# WIF_PCB.net
KiCad netlist of a schematic drawn in EasyEDA Pro
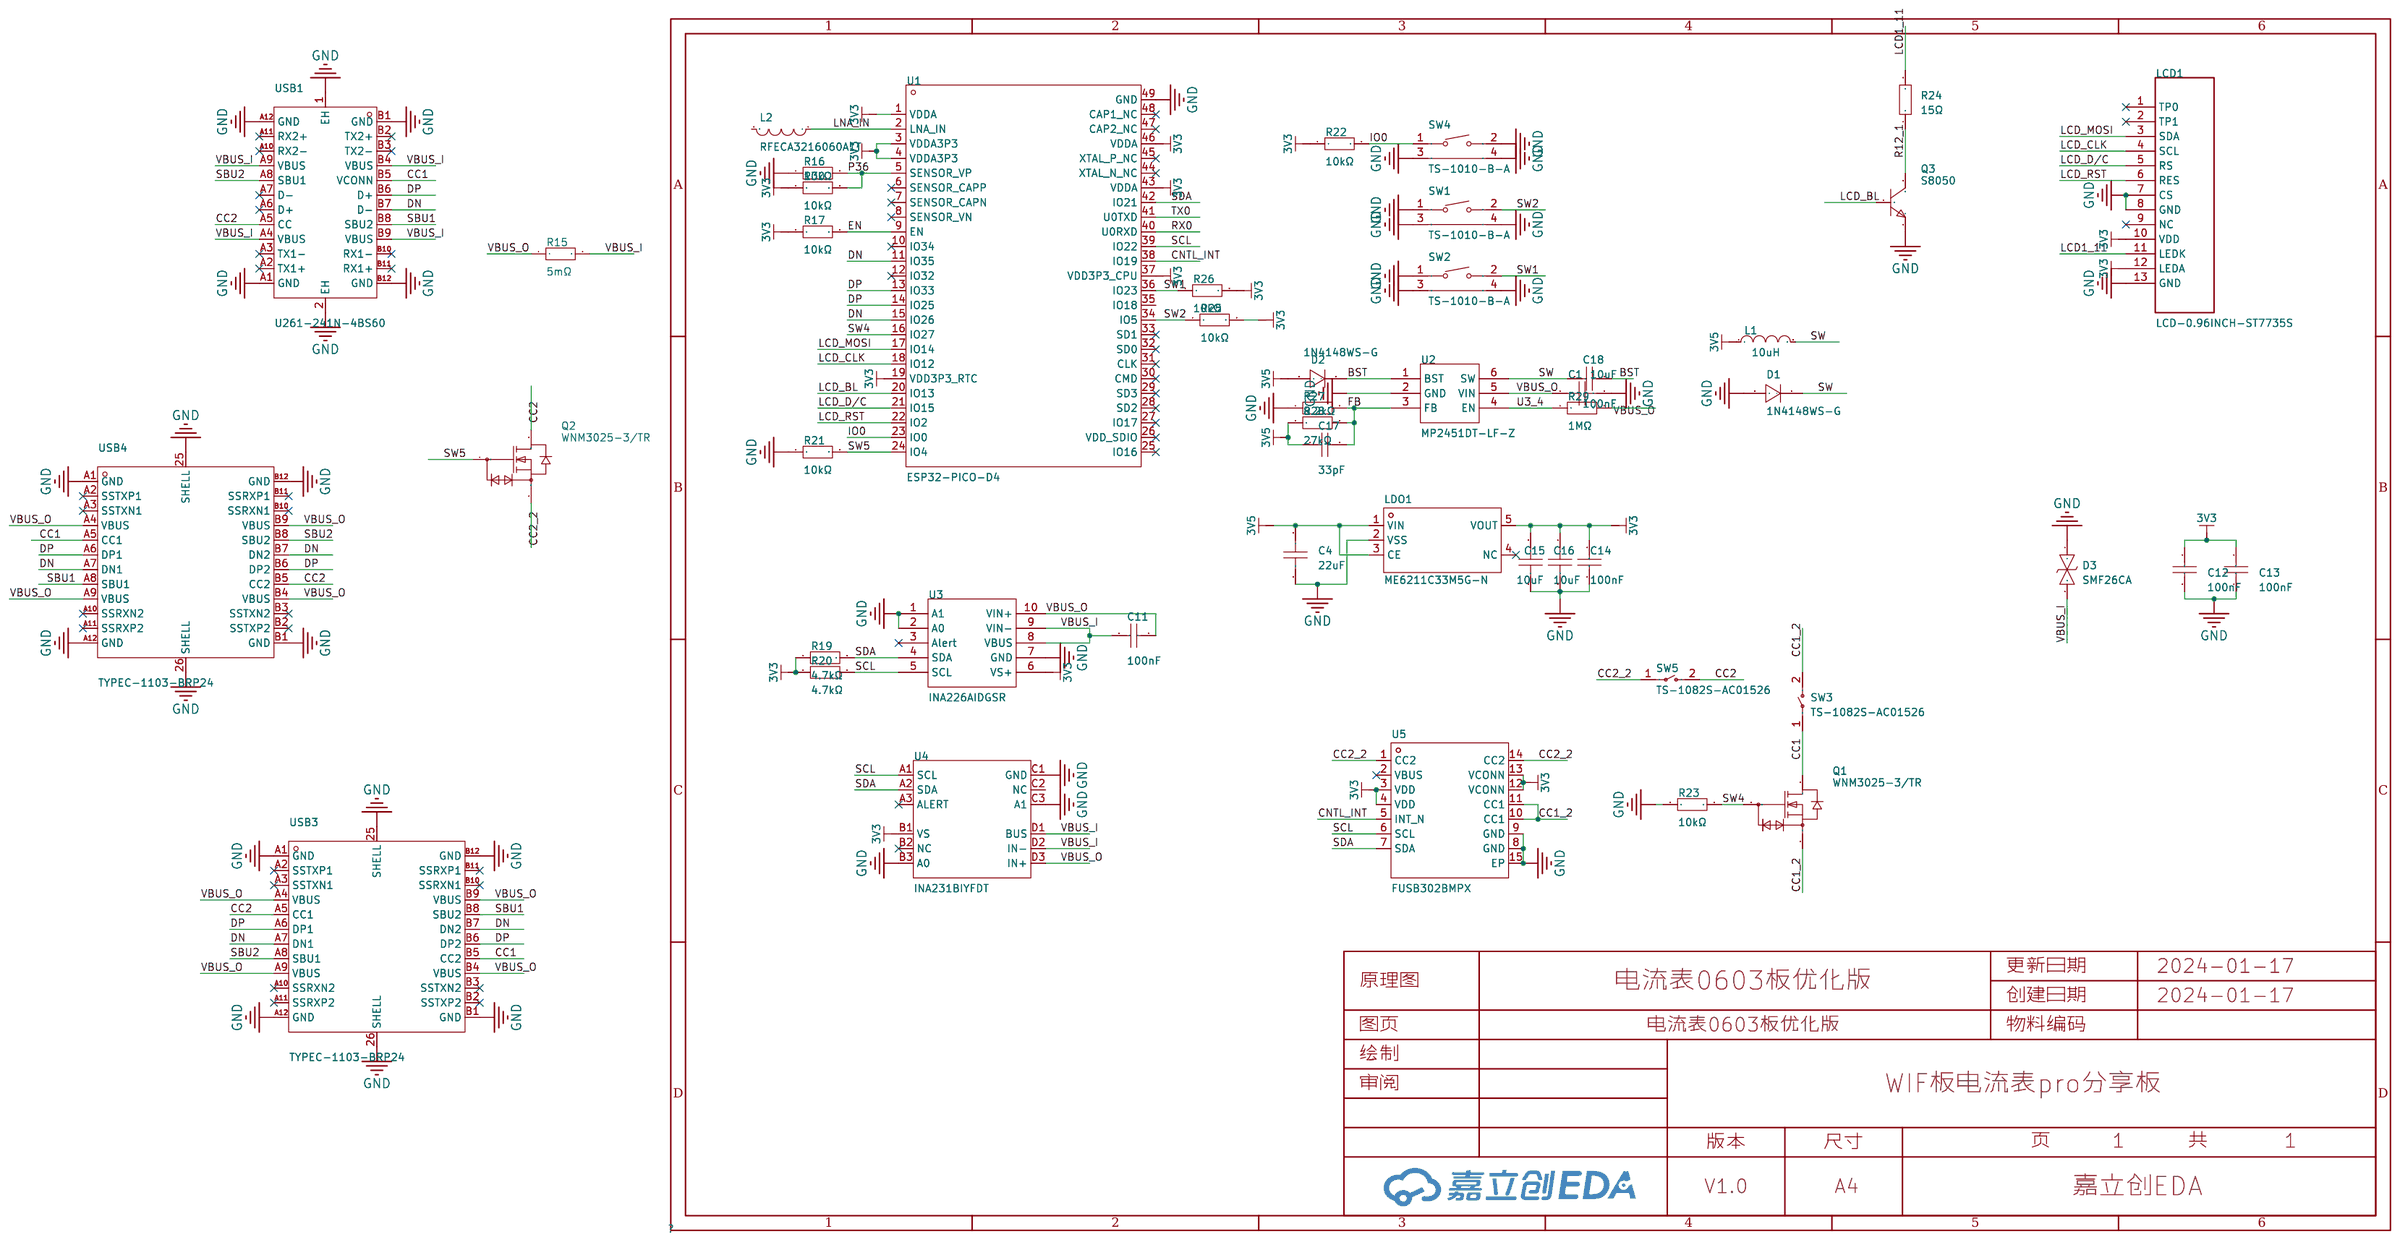
[diagram p0: schematic sheet]

(export (version "E")
  (design (tool "Eeschema 10.0.6"))
  (components
    (comp (ref "C1")
      (value "10uF")
      (footprint "easyedapro:C0603")
      (description "容值:10uF;精度:±20%;额定电压:25V;材质(温度系数):X5R;")
      (fields
        (field (name "Manufacturer Part") "CL10A106MA8NRNC")
        (field (name "Manufacturer") "SAMSUNG(三星)")
      )
      (libsource (lib "easyedapro") (part "CL10A106MA8NRNC"))
    )
    (comp (ref "C4")
      (value "22uF")
      (footprint "easyedapro:C0603")
      (description "容值:22uF;精度:±20%;额定电压:6.3V;材质(温度系数):X5R;")
      (fields
        (field (name "Manufacturer Part") "CL10A226MQ8NRNC")
        (field (name "Manufacturer") "SAMSUNG(三星)")
      )
      (libsource (lib "easyedapro") (part "CL10A226MQ8NRNC"))
    )
    (comp (ref "C11")
      (value "100nF")
      (footprint "easyedapro:C0603")
      (description "容值:100nF;精度:±10%;额定电压:50V;材质(温度系数):X7R;")
      (fields (field (name "Manufacturer Part") "0603B104K500NT") (field (name "Manufacturer") "FH(风华)"))
      (libsource (lib "easyedapro") (part "0603B104K500NT"))
    )
    (comp (ref "C12")
      (value "100nF")
      (footprint "easyedapro:C0603")
      (description "容值:100nF;精度:±10%;额定电压:50V;材质(温度系数):X7R;")
      (fields (field (name "Manufacturer Part") "0603B104K500NT") (field (name "Manufacturer") "FH(风华)"))
      (libsource (lib "easyedapro") (part "0603B104K500NT"))
    )
    (comp (ref "C13")
      (value "100nF")
      (footprint "easyedapro:C0603")
      (description "容值:100nF;精度:±10%;额定电压:50V;材质(温度系数):X7R;")
      (fields (field (name "Manufacturer Part") "0603B104K500NT") (field (name "Manufacturer") "FH(风华)"))
      (libsource (lib "easyedapro") (part "0603B104K500NT"))
    )
    (comp (ref "C14")
      (value "100nF")
      (footprint "easyedapro:C0603")
      (description "容值:100nF;精度:±10%;额定电压:50V;材质(温度系数):X7R;")
      (fields (field (name "Manufacturer Part") "0603B104K500NT") (field (name "Manufacturer") "FH(风华)"))
      (libsource (lib "easyedapro") (part "0603B104K500NT"))
    )
    (comp (ref "C15")
      (value "10uF")
      (footprint "easyedapro:C0603")
      (description "容值:10uF;精度:±10%;额定电压:10V;材质(温度系数):X5R;")
      (fields
        (field (name "Manufacturer Part") "CL10A106KP8NNNC")
        (field (name "Manufacturer") "SAMSUNG(三星)")
      )
      (libsource (lib "easyedapro") (part "CL10A106KP8NNNC"))
    )
    (comp (ref "C16")
      (value "10uF")
      (footprint "easyedapro:C0603")
      (description "容值:10uF;精度:±10%;额定电压:10V;材质(温度系数):X5R;")
      (fields
        (field (name "Manufacturer Part") "CL10A106KP8NNNC")
        (field (name "Manufacturer") "SAMSUNG(三星)")
      )
      (libsource (lib "easyedapro") (part "CL10A106KP8NNNC"))
    )
    (comp (ref "C17")
      (value "33pF")
      (footprint "easyedapro:C0603")
      (description "容值:33pF;精度:±5%;额定电压:50V;材质(温度系数):C0G;")
      (fields
        (field (name "Manufacturer Part") "CL10C330JB8NNNC")
        (field (name "Manufacturer") "SAMSUNG(三星)")
      )
      (libsource (lib "easyedapro") (part "CL10C330JB8NNNC"))
    )
    (comp (ref "C18")
      (value "100nF")
      (footprint "easyedapro:C0603")
      (description "容值:100nF;精度:±10%;额定电压:50V;材质(温度系数):X7R;")
      (fields (field (name "Manufacturer Part") "0603B104K500NT") (field (name "Manufacturer") "FH(风华)"))
      (libsource (lib "easyedapro") (part "0603B104K500NT"))
    )
    (comp (ref "D1")
      (value "1N4148WS-G")
      (footprint "easyedapro:SOD-323_L1.7-W1.3-LS2.7-RD")
      (description "二极管配置:独立式;正向压降(Vf):1.25V@150mA;直流反向耐压(Vr):100V;平均整流电流(Io):150mA;功率:200mW;反向恢复时间(trr):4ns;")
      (fields (field (name "Manufacturer") "CJ(江苏长电/长晶)"))
      (libsource (lib "easyedapro") (part "1N4148WS-G"))
    )
    (comp (ref "D2")
      (value "1N4148WS-G")
      (footprint "easyedapro:SOD-323_L1.7-W1.3-LS2.7-RD")
      (description "二极管配置:独立式;正向压降(Vf):1.25V@150mA;直流反向耐压(Vr):100V;平均整流电流(Io):150mA;功率:200mW;反向恢复时间(trr):4ns;")
      (fields (field (name "Manufacturer") "CJ(江苏长电/长晶)"))
      (libsource (lib "easyedapro") (part "1N4148WS-G"))
    )
    (comp (ref "D3")
      (value "SMF26CA")
      (footprint "easyedapro:SOD-123_L2.8-W1.8-LS3.7-BI")
      (description "极性:双向;反向截止电压(Vrwm):26V;击穿电压:28.9V;峰值脉冲电流(Ipp)@10/1000μs:4.8A;最大钳位电压:42.1V;")
      (fields (field (name "Manufacturer") "AnBon(安邦)"))
      (libsource (lib "easyedapro") (part "SMF26CA_C435495"))
    )
    (comp (ref "L1")
      (value "10uH")
      (footprint "easyedapro:IND-SMD_L4.4-W4.0_PHC0420")
      (description "电感值:10uH;精度:±20%;额定电流:1.6A;")
      (fields (field (name "Manufacturer Part") "PHC0420-100M-T") (field (name "Manufacturer") "EMTEK(兆欣)"))
      (libsource (lib "easyedapro") (part "PHC0420-100M-T"))
    )
    (comp (ref "L2")
      (value "RFECA3216060A1T")
      (footprint "easyedapro:ANT-SMD_L3.1-W1.6")
      (description "2.4 GHz 陶瓷天线")
      (fields (field (name "Manufacturer") "Walsin(华新科)"))
      (libsource (lib "easyedapro") (part "RFECA3216060A1T"))
    )
    (comp (ref "LCD1")
      (value "LCD-0.96INCH-ST7735S")
      (footprint "easyedapro:LCD-0.96INCH-IPS-TFT-16080-ST7735S")
      (libsource (lib "easyedapro") (part "LCD-0.96INCH-ST7735S-1"))
    )
    (comp (ref "LDO1")
      (value "ME6211C33M5G-N")
      (footprint "easyedapro:SOT-23-5_L3.0-W1.7-P0.95-LS2.8-BL")
      (description "输出类型:固定;输出极性:正;最大输入电压:6V;输出电压:3.3V;输出电流:500mA;电源纹波抑制比(PSRR):70dB;")
      (fields (field (name "Manufacturer") "MICRONE(南京微盟)"))
      (libsource (lib "easyedapro") (part "ME6211C33M5G-N"))
    )
    (comp (ref "Q1")
      (value "WNM3025-3/TR")
      (footprint "easyedapro:X1-DFN1006-3_L1.0-W0.6-P0.35-BR")
      (fields (field (name "Manufacturer") "WILLSEMI(韦尔)"))
      (libsource (lib "easyedapro") (part "WNM3025-3/TR"))
    )
    (comp (ref "Q2")
      (value "WNM3025-3/TR")
      (footprint "easyedapro:X1-DFN1006-3_L1.0-W0.6-P0.35-BR")
      (fields (field (name "Manufacturer") "WILLSEMI(韦尔)"))
      (libsource (lib "easyedapro") (part "WNM3025-3/TR"))
    )
    (comp (ref "Q3")
      (value "S8050")
      (footprint "easyedapro:SOT-23-3_L2.9-W1.3-P1.90-LS2.4-BR")
      (description "晶体管类型:-;集电极电流(Ic):500mA;集射极击穿电压(Vceo):25V;功率(Pd):300mW;")
      (fields (field (name "Manufacturer") "JSMSEMI(杰盛微)"))
      (libsource (lib "easyedapro") (part "S8050"))
    )
    (comp (ref "R15")
      (value "5mΩ")
      (footprint "easyedapro:R2512")
      (description "阻值:5mΩ;精度:±1%;功率:3W;温度系数:±25ppm/°C;")
      (fields (field (name "Manufacturer Part") "LR2512-23R005F4") (field (name "Manufacturer") "RALEC(旺诠)"))
      (libsource (lib "easyedapro") (part "LR2512-23R005F4"))
    )
    (comp (ref "R16")
      (value "10kΩ")
      (footprint "easyedapro:R0603")
      (description "阻值:10kΩ;精度:±1%;功率:100mW;温度系数:±100ppm/°C;电阻类型:厚膜电阻;")
      (fields
        (field (name "Manufacturer Part") "0603WAF1002T5E")
        (field (name "Manufacturer") "UNI-ROYAL(厚声)")
      )
      (libsource (lib "easyedapro") (part "0603WAF1002T5E"))
    )
    (comp (ref "R17")
      (value "10kΩ")
      (footprint "easyedapro:R0603")
      (description "阻值:10kΩ;精度:±1%;功率:100mW;温度系数:±100ppm/°C;电阻类型:厚膜电阻;")
      (fields
        (field (name "Manufacturer Part") "0603WAF1002T5E")
        (field (name "Manufacturer") "UNI-ROYAL(厚声)")
      )
      (libsource (lib "easyedapro") (part "0603WAF1002T5E"))
    )
    (comp (ref "R19")
      (value "4.7kΩ")
      (footprint "easyedapro:R0603")
      (description "阻值:4.7kΩ;精度:±1%;功率:100mW;温度系数:±100ppm/°C;电阻类型:厚膜电阻;")
      (fields
        (field (name "Manufacturer Part") "0603WAF4701T5E")
        (field (name "Manufacturer") "UNI-ROYAL(厚声)")
      )
      (libsource (lib "easyedapro") (part "0603WAF4701T5E"))
    )
    (comp (ref "R20")
      (value "4.7kΩ")
      (footprint "easyedapro:R0603")
      (description "阻值:4.7kΩ;精度:±1%;功率:100mW;温度系数:±100ppm/°C;电阻类型:厚膜电阻;")
      (fields
        (field (name "Manufacturer Part") "0603WAF4701T5E")
        (field (name "Manufacturer") "UNI-ROYAL(厚声)")
      )
      (libsource (lib "easyedapro") (part "0603WAF4701T5E"))
    )
    (comp (ref "R21")
      (value "10kΩ")
      (footprint "easyedapro:R0603")
      (description "阻值:10kΩ;精度:±1%;功率:100mW;温度系数:±100ppm/°C;电阻类型:厚膜电阻;")
      (fields
        (field (name "Manufacturer Part") "0603WAF1002T5E")
        (field (name "Manufacturer") "UNI-ROYAL(厚声)")
      )
      (libsource (lib "easyedapro") (part "0603WAF1002T5E"))
    )
    (comp (ref "R22")
      (value "10kΩ")
      (footprint "easyedapro:R0603")
      (description "阻值:10kΩ;精度:±1%;功率:100mW;温度系数:±100ppm/°C;电阻类型:厚膜电阻;")
      (fields
        (field (name "Manufacturer Part") "0603WAF1002T5E")
        (field (name "Manufacturer") "UNI-ROYAL(厚声)")
      )
      (libsource (lib "easyedapro") (part "0603WAF1002T5E"))
    )
    (comp (ref "R23")
      (value "10kΩ")
      (footprint "easyedapro:R0603")
      (description "阻值:10kΩ;精度:±1%;功率:100mW;温度系数:±100ppm/°C;电阻类型:厚膜电阻;")
      (fields
        (field (name "Manufacturer Part") "0603WAF1002T5E")
        (field (name "Manufacturer") "UNI-ROYAL(厚声)")
      )
      (libsource (lib "easyedapro") (part "0603WAF1002T5E"))
    )
    (comp (ref "R24")
      (value "15Ω")
      (footprint "easyedapro:R0603")
      (description "阻值:15Ω;精度:±1%;功率:100mW;温度系数:±100ppm/°C;电阻类型:厚膜电阻;")
      (fields
        (field (name "Manufacturer Part") "0603WAF150JT5E")
        (field (name "Manufacturer") "UNI-ROYAL(厚声)")
      )
      (libsource (lib "easyedapro") (part "0603WAF150JT5E"))
    )
    (comp (ref "R25")
      (value "10kΩ")
      (footprint "easyedapro:R0603")
      (description "阻值:10kΩ;精度:±1%;功率:100mW;温度系数:±100ppm/°C;电阻类型:厚膜电阻;")
      (fields
        (field (name "Manufacturer Part") "0603WAF1002T5E")
        (field (name "Manufacturer") "UNI-ROYAL(厚声)")
      )
      (libsource (lib "easyedapro") (part "0603WAF1002T5E"))
    )
    (comp (ref "R26")
      (value "10kΩ")
      (footprint "easyedapro:R0603")
      (description "阻值:10kΩ;精度:±1%;功率:100mW;温度系数:±100ppm/°C;电阻类型:厚膜电阻;")
      (fields
        (field (name "Manufacturer Part") "0603WAF1002T5E")
        (field (name "Manufacturer") "UNI-ROYAL(厚声)")
      )
      (libsource (lib "easyedapro") (part "0603WAF1002T5E"))
    )
    (comp (ref "R27")
      (value "8.2kΩ")
      (footprint "easyedapro:R0603")
      (description "阻值:8.2kΩ;精度:±1%;功率:100mW;温度系数:±100ppm/°C;电阻类型:厚膜电阻;")
      (fields
        (field (name "Manufacturer Part") "0603WAF8201T5E")
        (field (name "Manufacturer") "UNI-ROYAL(厚声)")
      )
      (libsource (lib "easyedapro") (part "0603WAF8201T5E"))
    )
    (comp (ref "R28")
      (value "27kΩ")
      (footprint "easyedapro:R0603")
      (description "阻值:27kΩ;精度:±1%;功率:100mW;温度系数:±100ppm/°C;电阻类型:厚膜电阻;")
      (fields
        (field (name "Manufacturer Part") "0603WAF2702T5E")
        (field (name "Manufacturer") "UNI-ROYAL(厚声)")
      )
      (libsource (lib "easyedapro") (part "0603WAF2702T5E"))
    )
    (comp (ref "R29")
      (value "1MΩ")
      (footprint "easyedapro:R0603")
      (description "阻值:1MΩ;精度:±1%;功率:100mW;温度系数:±100ppm/°C;电阻类型:厚膜电阻;")
      (fields
        (field (name "Manufacturer Part") "0603WAF1004T5E")
        (field (name "Manufacturer") "UNI-ROYAL(厚声)")
      )
      (libsource (lib "easyedapro") (part "0603WAF1004T5E"))
    )
    (comp (ref "R30")
      (value "10kΩ")
      (footprint "easyedapro:R0402")
      (description "电阻类型:厚膜电阻;阻值:10kΩ;精度:±1%;功率:62.5mW;")
      (fields (field (name "Manufacturer Part") "RC0402FR-0710KL") (field (name "Manufacturer") "YAGEO(国巨)"))
      (libsource (lib "easyedapro") (part "RC0402FR-0710KL"))
    )
    (comp (ref "SW1")
      (value "TS-1010-B-A")
      (footprint "easyedapro:KEY-SMD_TX-1010-X-X")
      (description "触点电流:50mA;额定电压(DC):12V;绝缘电阻:-;电路结构:单刀单掷;安装方式:卧贴;带灯:无;作用力:160gf;机械寿命:10万次;带支架:否;")
      (fields (field (name "Manufacturer") "XKB Connectivity(中国星坤)"))
      (libsource (lib "easyedapro") (part "TS-1010-B-A"))
    )
    (comp (ref "SW2")
      (value "TS-1010-B-A")
      (footprint "easyedapro:KEY-SMD_TX-1010-X-X")
      (description "触点电流:50mA;额定电压(DC):12V;绝缘电阻:-;电路结构:单刀单掷;安装方式:卧贴;带灯:无;作用力:160gf;机械寿命:10万次;带支架:否;")
      (fields (field (name "Manufacturer") "XKB Connectivity(中国星坤)"))
      (libsource (lib "easyedapro") (part "TS-1010-B-A"))
    )
    (comp (ref "SW3")
      (value "TS-1082S-AC01526")
      (footprint "easyedapro:SW-SMD_L3.9-W3.6-LS4.8-EH")
      (description "电路结构:单刀单掷;触点电流:50mA;额定电压(DC):12V;安装方式:卧贴;绝缘电阻:100MΩ;作用力:260gf@±50gf;机械寿命:10万次;")
      (fields (field (name "Manufacturer") "XUNPU(讯普)"))
      (libsource (lib "easyedapro") (part "TS-1082S-AC01526"))
    )
    (comp (ref "SW4")
      (value "TS-1010-B-A")
      (footprint "easyedapro:KEY-SMD_TX-1010-X-X")
      (description "触点电流:50mA;额定电压(DC):12V;绝缘电阻:-;电路结构:单刀单掷;安装方式:卧贴;带灯:无;作用力:160gf;机械寿命:10万次;带支架:否;")
      (fields (field (name "Manufacturer") "XKB Connectivity(中国星坤)"))
      (libsource (lib "easyedapro") (part "TS-1010-B-A"))
    )
    (comp (ref "SW5")
      (value "TS-1082S-AC01526")
      (footprint "easyedapro:SW-SMD_L3.9-W3.6-LS4.8-EH")
      (description "电路结构:单刀单掷;触点电流:50mA;额定电压(DC):12V;安装方式:卧贴;绝缘电阻:100MΩ;作用力:260gf@±50gf;机械寿命:10万次;")
      (fields (field (name "Manufacturer") "XUNPU(讯普)"))
      (libsource (lib "easyedapro") (part "TS-1082S-AC01526"))
    )
    (comp (ref "U1")
      (value "ESP32-PICO-D4")
      (footprint "easyedapro:LGA-48_L7.0-W7.0-P0.50-BL-EP5.4")
      (fields (field (name "Manufacturer") "ESPRESSIF(乐鑫)"))
      (libsource (lib "easyedapro") (part "ESP32-PICO-D4"))
    )
    (comp (ref "U2")
      (value "MP2451DT-LF-Z")
      (footprint "easyedapro:SOT-23-6_L2.9-W1.6-P0.95-LS2.8-BR")
      (description "最大输入电压:-;可输出电流:-;")
      (libsource (lib "easyedapro") (part "MP2451DT-LF-Z"))
    )
    (comp (ref "U3")
      (value "INA226AIDGSR")
      (footprint "easyedapro:MSOP-10_L3.0-W3.0-P0.50-LS5.0-BL")
      (description "INA226 支持报警功能的 36V、双向、超高精度、低侧/高侧、I2C 输出电流/功率监控器")
      (fields (field (name "Manufacturer") "TI(德州仪器)"))
      (libsource (lib "easyedapro") (part "INA226AIDGSR"))
    )
    (comp (ref "U4")
      (value "INA231BIYFDT")
      (footprint "easyedapro:DSBGA-12_L1.7-W1.4-R3-C4-P0.40-BL")
      (description "采用 WCSP 封装的 28V、16 位、I2C 输出电流/电压/功率监控器 12-DSBGA -40 to 125")
      (fields (field (name "Manufacturer") "TI(德州仪器)"))
      (libsource (lib "easyedapro") (part "INA231BIYFDT"))
    )
    (comp (ref "U5")
      (value "FUSB302BMPX")
      (footprint "easyedapro:MLP-14_L2.5-W2.5-P0.50-BL-EP")
      (description "应用功能:-;接口协议:-;")
      (fields (field (name "Manufacturer") "onsemi(安森美)"))
      (libsource (lib "easyedapro") (part "FUSB302BMPX"))
    )
    (comp (ref "USB1")
      (value "U261-241N-4BS60")
      (footprint "easyedapro:USB-TYPE-C-SMD_U261-241N-4BS60")
      (fields (field (name "Manufacturer") "XKB Connectivity(中国星坤)"))
      (libsource (lib "easyedapro") (part "U261-241N-4BS60"))
    )
    (comp (ref "USB3")
      (value "TYPEC-1103-BRP24")
      (footprint "easyedapro:USB-C-SMD_TYPEC-1103-BRP24")
      (fields (field (name "Manufacturer") "XUNPU(讯普)"))
      (libsource (lib "easyedapro") (part "TYPEC-1103-BRP24"))
    )
    (comp (ref "USB4")
      (value "TYPEC-1103-BRP24")
      (footprint "easyedapro:USB-C-SMD_TYPEC-1103-BRP24")
      (fields (field (name "Manufacturer") "XUNPU(讯普)"))
      (libsource (lib "easyedapro") (part "TYPEC-1103-BRP24"))
    )
  )
  (nets
    (net (code "1") (name "/BST") (class "Default")
      (node (ref "C18") (pin "2") (pinfunction "2_2") (pintype "input"))
      (node (ref "D2") (pin "1") (pinfunction "-_1") (pintype "unspecified"))
      (node (ref "U2") (pin "1") (pinfunction "BST_1") (pintype "input"))
    )
    (net (code "2") (name "/CC1") (class "Default")
      (node (ref "Q1") (pin "3") (pinfunction "D_3") (pintype "unspecified"))
      (node (ref "SW3") (pin "1") (pinfunction "1_1") (pintype "unspecified"))
      (node (ref "USB1") (pin "B5") (pinfunction "VCONN_B5") (pintype "unspecified"))
      (node (ref "USB3") (pin "B5") (pinfunction "CC2_B5") (pintype "unspecified"))
      (node (ref "USB4") (pin "A5") (pinfunction "CC1_A5") (pintype "unspecified"))
    )
    (net (code "3") (name "/CC1_2") (class "Default")
      (node (ref "Q1") (pin "2") (pinfunction "S_2") (pintype "unspecified"))
      (node (ref "SW3") (pin "2") (pinfunction "2_2") (pintype "unspecified"))
      (node (ref "U5") (pin "10") (pinfunction "CC1_10") (pintype "input"))
      (node (ref "U5") (pin "11") (pinfunction "CC1_11") (pintype "input"))
    )
    (net (code "4") (name "/CC2") (class "Default")
      (node (ref "Q2") (pin "3") (pinfunction "D_3") (pintype "unspecified"))
      (node (ref "SW5") (pin "2") (pinfunction "2_2") (pintype "unspecified"))
      (node (ref "USB1") (pin "A5") (pinfunction "CC_A5") (pintype "unspecified"))
      (node (ref "USB3") (pin "A5") (pinfunction "CC1_A5") (pintype "unspecified"))
      (node (ref "USB4") (pin "B5") (pinfunction "CC2_B5") (pintype "unspecified"))
    )
    (net (code "5") (name "/CC2_2") (class "Default")
      (node (ref "Q2") (pin "2") (pinfunction "S_2") (pintype "unspecified"))
      (node (ref "SW5") (pin "1") (pinfunction "1_1") (pintype "unspecified"))
      (node (ref "U5") (pin "1") (pinfunction "CC2_1") (pintype "input"))
      (node (ref "U5") (pin "14") (pinfunction "CC2_14") (pintype "input"))
    )
    (net (code "6") (name "/CNTL_INT") (class "Default")
      (node (ref "U1") (pin "38") (pinfunction "IO19_38") (pintype "unspecified"))
      (node (ref "U5") (pin "5") (pinfunction "INT_N_5") (pintype "input"))
    )
    (net (code "7") (name "/DN") (class "Default")
      (node (ref "U1") (pin "11") (pinfunction "IO35_11") (pintype "unspecified"))
      (node (ref "U1") (pin "15") (pinfunction "IO26_15") (pintype "unspecified"))
      (node (ref "USB1") (pin "B7") (pinfunction "D-_B7") (pintype "unspecified"))
      (node (ref "USB3") (pin "A7") (pinfunction "DN1_A7") (pintype "unspecified"))
      (node (ref "USB3") (pin "B7") (pinfunction "DN2_B7") (pintype "unspecified"))
      (node (ref "USB4") (pin "A7") (pinfunction "DN1_A7") (pintype "unspecified"))
      (node (ref "USB4") (pin "B7") (pinfunction "DN2_B7") (pintype "unspecified"))
    )
    (net (code "8") (name "/DP") (class "Default")
      (node (ref "U1") (pin "13") (pinfunction "IO33_13") (pintype "unspecified"))
      (node (ref "U1") (pin "14") (pinfunction "IO25_14") (pintype "unspecified"))
      (node (ref "USB1") (pin "B6") (pinfunction "D+_B6") (pintype "unspecified"))
      (node (ref "USB3") (pin "A6") (pinfunction "DP1_A6") (pintype "unspecified"))
      (node (ref "USB3") (pin "B6") (pinfunction "DP2_B6") (pintype "unspecified"))
      (node (ref "USB4") (pin "A6") (pinfunction "DP1_A6") (pintype "unspecified"))
      (node (ref "USB4") (pin "B6") (pinfunction "DP2_B6") (pintype "unspecified"))
    )
    (net (code "9") (name "/EN") (class "Default")
      (node (ref "R17") (pin "2") (pinfunction "2_2") (pintype "input"))
      (node (ref "U1") (pin "9") (pinfunction "EN_9") (pintype "unspecified"))
    )
    (net (code "10") (name "/FB") (class "Default")
      (node (ref "C17") (pin "2") (pinfunction "2_2") (pintype "input"))
      (node (ref "R27") (pin "2") (pinfunction "2_2") (pintype "input"))
      (node (ref "R28") (pin "2") (pinfunction "2_2") (pintype "input"))
      (node (ref "U2") (pin "3") (pinfunction "FB_3") (pintype "input"))
    )
    (net (code "11") (name "/IO0") (class "Default")
      (node (ref "R22") (pin "2") (pinfunction "2_2") (pintype "input"))
      (node (ref "SW4") (pin "1") (pinfunction "1_1") (pintype "input"))
      (node (ref "U1") (pin "23") (pinfunction "IO0_23") (pintype "unspecified"))
    )
    (net (code "12") (name "/LCD1_11") (class "Default")
      (node (ref "LCD1") (pin "11") (pinfunction "LEDK_11") (pintype "input"))
      (node (ref "R24") (pin "2") (pinfunction "2_2") (pintype "input"))
    )
    (net (code "13") (name "/LCD_BL") (class "Default")
      (node (ref "Q3") (pin "1") (pinfunction "B_1") (pintype "input"))
      (node (ref "U1") (pin "20") (pinfunction "IO13_20") (pintype "unspecified"))
    )
    (net (code "14") (name "/LCD_CLK") (class "Default")
      (node (ref "LCD1") (pin "4") (pinfunction "SCL_4") (pintype "input"))
      (node (ref "U1") (pin "18") (pinfunction "IO12_18") (pintype "unspecified"))
    )
    (net (code "15") (name "/LCD_D{slash}C") (class "Default")
      (node (ref "LCD1") (pin "5") (pinfunction "RS_5") (pintype "input"))
      (node (ref "U1") (pin "21") (pinfunction "IO15_21") (pintype "unspecified"))
    )
    (net (code "16") (name "/LCD_MOSI") (class "Default")
      (node (ref "LCD1") (pin "3") (pinfunction "SDA_3") (pintype "input"))
      (node (ref "U1") (pin "17") (pinfunction "IO14_17") (pintype "unspecified"))
    )
    (net (code "17") (name "/LCD_RST") (class "Default")
      (node (ref "LCD1") (pin "6") (pinfunction "RES_6") (pintype "input"))
      (node (ref "U1") (pin "22") (pinfunction "IO2_22") (pintype "unspecified"))
    )
    (net (code "18") (name "/LNA_IN") (class "Default")
      (node (ref "L2") (pin "1") (pinfunction "1_1") (pintype "input"))
      (node (ref "U1") (pin "2") (pinfunction "LNA_IN_2") (pintype "unspecified"))
    )
    (net (code "19") (name "/P36") (class "Default")
      (node (ref "R16") (pin "2") (pinfunction "2_2") (pintype "input"))
      (node (ref "R30") (pin "2") (pinfunction "2_2") (pintype "input"))
      (node (ref "U1") (pin "5") (pinfunction "SENSOR_VP_5") (pintype "unspecified"))
    )
    (net (code "20") (name "/R12_1") (class "Default")
      (node (ref "Q3") (pin "3") (pinfunction "C_3") (pintype "input"))
      (node (ref "R24") (pin "1") (pinfunction "1_1") (pintype "input"))
    )
    (net (code "21") (name "/RX0") (class "Default")
      (node (ref "U1") (pin "40") (pinfunction "U0RXD_40") (pintype "unspecified"))
    )
    (net (code "22") (name "/SBU1") (class "Default")
      (node (ref "USB1") (pin "B8") (pinfunction "SBU2_B8") (pintype "unspecified"))
      (node (ref "USB3") (pin "B8") (pinfunction "SBU2_B8") (pintype "unspecified"))
      (node (ref "USB4") (pin "A8") (pinfunction "SBU1_A8") (pintype "unspecified"))
    )
    (net (code "23") (name "/SBU2") (class "Default")
      (node (ref "USB1") (pin "A8") (pinfunction "SBU1_A8") (pintype "unspecified"))
      (node (ref "USB3") (pin "A8") (pinfunction "SBU1_A8") (pintype "unspecified"))
      (node (ref "USB4") (pin "B8") (pinfunction "SBU2_B8") (pintype "unspecified"))
    )
    (net (code "24") (name "/SCL") (class "Default")
      (node (ref "R20") (pin "2") (pinfunction "2_2") (pintype "input"))
      (node (ref "U1") (pin "39") (pinfunction "IO22_39") (pintype "unspecified"))
      (node (ref "U3") (pin "5") (pinfunction "SCL_5") (pintype "unspecified"))
      (node (ref "U4") (pin "A1") (pinfunction "SCL_A1") (pintype "input"))
      (node (ref "U5") (pin "6") (pinfunction "SCL_6") (pintype "input"))
    )
    (net (code "25") (name "/SDA") (class "Default")
      (node (ref "R19") (pin "2") (pinfunction "2_2") (pintype "input"))
      (node (ref "U1") (pin "42") (pinfunction "IO21_42") (pintype "unspecified"))
      (node (ref "U3") (pin "4") (pinfunction "SDA_4") (pintype "unspecified"))
      (node (ref "U4") (pin "A2") (pinfunction "SDA_A2") (pintype "input"))
      (node (ref "U5") (pin "7") (pinfunction "SDA_7") (pintype "input"))
    )
    (net (code "26") (name "/SW") (class "Default")
      (node (ref "C18") (pin "1") (pinfunction "1_1") (pintype "input"))
      (node (ref "D1") (pin "1") (pinfunction "-_1") (pintype "unspecified"))
      (node (ref "L1") (pin "2") (pinfunction "2_2") (pintype "input"))
      (node (ref "U2") (pin "6") (pinfunction "SW_6") (pintype "input"))
    )
    (net (code "27") (name "/SW1") (class "Default")
      (node (ref "R26") (pin "1") (pinfunction "1_1") (pintype "input"))
      (node (ref "SW2") (pin "2") (pinfunction "2_2") (pintype "input"))
      (node (ref "U1") (pin "36") (pinfunction "IO23_36") (pintype "unspecified"))
    )
    (net (code "28") (name "/SW2") (class "Default")
      (node (ref "R25") (pin "1") (pinfunction "1_1") (pintype "input"))
      (node (ref "SW1") (pin "2") (pinfunction "2_2") (pintype "input"))
      (node (ref "U1") (pin "34") (pinfunction "IO5_34") (pintype "unspecified"))
    )
    (net (code "29") (name "/SW4") (class "Default")
      (node (ref "Q1") (pin "1") (pinfunction "G_1") (pintype "unspecified"))
      (node (ref "R23") (pin "2") (pinfunction "2_2") (pintype "input"))
      (node (ref "U1") (pin "16") (pinfunction "IO27_16") (pintype "unspecified"))
    )
    (net (code "30") (name "/SW5") (class "Default")
      (node (ref "Q2") (pin "1") (pinfunction "G_1") (pintype "unspecified"))
      (node (ref "R21") (pin "2") (pinfunction "2_2") (pintype "input"))
      (node (ref "U1") (pin "24") (pinfunction "IO4_24") (pintype "unspecified"))
    )
    (net (code "31") (name "/TX0") (class "Default")
      (node (ref "U1") (pin "41") (pinfunction "U0TXD_41") (pintype "unspecified"))
    )
    (net (code "32") (name "/U3_4") (class "Default")
      (node (ref "R29") (pin "1") (pinfunction "1_1") (pintype "input"))
      (node (ref "U2") (pin "4") (pinfunction "EN_4") (pintype "input"))
    )
    (net (code "33") (name "/VBUS_I") (class "Default")
      (node (ref "C11") (pin "1") (pinfunction "1_1") (pintype "input"))
      (node (ref "D3") (pin "2") (pinfunction "2_2") (pintype "input"))
      (node (ref "R15") (pin "2") (pinfunction "2_2") (pintype "unspecified"))
      (node (ref "U3") (pin "8") (pinfunction "VBUS_8") (pintype "unspecified"))
      (node (ref "U3") (pin "9") (pinfunction "VIN-_9") (pintype "unspecified"))
      (node (ref "U4") (pin "D1") (pinfunction "BUS_D1") (pintype "input"))
      (node (ref "U4") (pin "D2") (pinfunction "IN-_D2") (pintype "input"))
      (node (ref "USB1") (pin "A4") (pinfunction "VBUS_A4") (pintype "unspecified"))
      (node (ref "USB1") (pin "A9") (pinfunction "VBUS_A9") (pintype "unspecified"))
      (node (ref "USB1") (pin "B4") (pinfunction "VBUS_B4") (pintype "unspecified"))
      (node (ref "USB1") (pin "B9") (pinfunction "VBUS_B9") (pintype "unspecified"))
    )
    (net (code "34") (name "/VBUS_O") (class "Default")
      (node (ref "C1") (pin "1") (pinfunction "1_1") (pintype "unspecified"))
      (node (ref "C11") (pin "2") (pinfunction "2_2") (pintype "input"))
      (node (ref "R15") (pin "1") (pinfunction "1_1") (pintype "unspecified"))
      (node (ref "R29") (pin "2") (pinfunction "2_2") (pintype "input"))
      (node (ref "U2") (pin "5") (pinfunction "VIN_5") (pintype "input"))
      (node (ref "U3") (pin "10") (pinfunction "VIN+_10") (pintype "unspecified"))
      (node (ref "U4") (pin "D3") (pinfunction "IN+_D3") (pintype "input"))
      (node (ref "USB3") (pin "A4") (pinfunction "VBUS_A4") (pintype "unspecified"))
      (node (ref "USB3") (pin "A9") (pinfunction "VBUS_A9") (pintype "unspecified"))
      (node (ref "USB3") (pin "B4") (pinfunction "VBUS_B4") (pintype "unspecified"))
      (node (ref "USB3") (pin "B9") (pinfunction "VBUS_B9") (pintype "unspecified"))
      (node (ref "USB4") (pin "A4") (pinfunction "VBUS_A4") (pintype "unspecified"))
      (node (ref "USB4") (pin "A9") (pinfunction "VBUS_A9") (pintype "unspecified"))
      (node (ref "USB4") (pin "B4") (pinfunction "VBUS_B4") (pintype "unspecified"))
      (node (ref "USB4") (pin "B9") (pinfunction "VBUS_B9") (pintype "unspecified"))
    )
    (net (code "35") (name "3V3") (class "Default")
      (node (ref "C12") (pin "2") (pinfunction "2_2") (pintype "input"))
      (node (ref "C13") (pin "2") (pinfunction "2_2") (pintype "input"))
      (node (ref "C14") (pin "2") (pinfunction "2_2") (pintype "input"))
      (node (ref "C15") (pin "2") (pinfunction "2_2") (pintype "unspecified"))
      (node (ref "C16") (pin "2") (pinfunction "2_2") (pintype "unspecified"))
      (node (ref "LCD1") (pin "10") (pinfunction "VDD_10") (pintype "input"))
      (node (ref "LCD1") (pin "12") (pinfunction "LEDA_12") (pintype "input"))
      (node (ref "LDO1") (pin "5") (pinfunction "VOUT_5") (pintype "input"))
      (node (ref "R17") (pin "1") (pinfunction "1_1") (pintype "input"))
      (node (ref "R19") (pin "1") (pinfunction "1_1") (pintype "input"))
      (node (ref "R20") (pin "1") (pinfunction "1_1") (pintype "input"))
      (node (ref "R22") (pin "1") (pinfunction "1_1") (pintype "input"))
      (node (ref "R25") (pin "2") (pinfunction "2_2") (pintype "input"))
      (node (ref "R26") (pin "2") (pinfunction "2_2") (pintype "input"))
      (node (ref "R30") (pin "1") (pinfunction "1_1") (pintype "input"))
      (node (ref "U1") (pin "1") (pinfunction "VDDA_1") (pintype "unspecified"))
      (node (ref "U1") (pin "19") (pinfunction "VDD3P3_RTC_19") (pintype "unspecified"))
      (node (ref "U1") (pin "3") (pinfunction "VDDA3P3_3") (pintype "unspecified"))
      (node (ref "U1") (pin "37") (pinfunction "VDD3P3_CPU_37") (pintype "unspecified"))
      (node (ref "U1") (pin "4") (pinfunction "VDDA3P3_4") (pintype "unspecified"))
      (node (ref "U1") (pin "43") (pinfunction "VDDA_43") (pintype "unspecified"))
      (node (ref "U1") (pin "46") (pinfunction "VDDA_46") (pintype "unspecified"))
      (node (ref "U3") (pin "6") (pinfunction "VS+_6") (pintype "unspecified"))
      (node (ref "U4") (pin "B1") (pinfunction "VS_B1") (pintype "input"))
      (node (ref "U5") (pin "12") (pinfunction "VCONN_12") (pintype "input"))
      (node (ref "U5") (pin "13") (pinfunction "VCONN_13") (pintype "input"))
      (node (ref "U5") (pin "3") (pinfunction "VDD_3") (pintype "input"))
      (node (ref "U5") (pin "4") (pinfunction "VDD_4") (pintype "input"))
    )
    (net (code "36") (name "3V5") (class "Default")
      (node (ref "C17") (pin "1") (pinfunction "1_1") (pintype "input"))
      (node (ref "C4") (pin "2") (pinfunction "2_2") (pintype "unspecified"))
      (node (ref "D2") (pin "2") (pinfunction "+_2") (pintype "unspecified"))
      (node (ref "L1") (pin "1") (pinfunction "1_1") (pintype "input"))
      (node (ref "LDO1") (pin "1") (pinfunction "VIN_1") (pintype "input"))
      (node (ref "LDO1") (pin "3") (pinfunction "CE_3") (pintype "input"))
      (node (ref "R28") (pin "1") (pinfunction "1_1") (pintype "input"))
    )
    (net (code "37") (name "GND") (class "Default")
      (node (ref "C1") (pin "2") (pinfunction "2_2") (pintype "unspecified"))
      (node (ref "C12") (pin "1") (pinfunction "1_1") (pintype "input"))
      (node (ref "C13") (pin "1") (pinfunction "1_1") (pintype "input"))
      (node (ref "C14") (pin "1") (pinfunction "1_1") (pintype "input"))
      (node (ref "C15") (pin "1") (pinfunction "1_1") (pintype "unspecified"))
      (node (ref "C16") (pin "1") (pinfunction "1_1") (pintype "unspecified"))
      (node (ref "C4") (pin "1") (pinfunction "1_1") (pintype "unspecified"))
      (node (ref "D1") (pin "2") (pinfunction "+_2") (pintype "unspecified"))
      (node (ref "D3") (pin "1") (pinfunction "1_1") (pintype "input"))
      (node (ref "LCD1") (pin "13") (pinfunction "GND_13") (pintype "input"))
      (node (ref "LCD1") (pin "7") (pinfunction "CS_7") (pintype "input"))
      (node (ref "LCD1") (pin "8") (pinfunction "GND_8") (pintype "input"))
      (node (ref "LDO1") (pin "2") (pinfunction "VSS_2") (pintype "input"))
      (node (ref "Q3") (pin "2") (pinfunction "E_2") (pintype "input"))
      (node (ref "R16") (pin "1") (pinfunction "1_1") (pintype "input"))
      (node (ref "R21") (pin "1") (pinfunction "1_1") (pintype "input"))
      (node (ref "R23") (pin "1") (pinfunction "1_1") (pintype "input"))
      (node (ref "R27") (pin "1") (pinfunction "1_1") (pintype "input"))
      (node (ref "SW1") (pin "1") (pinfunction "1_1") (pintype "input"))
      (node (ref "SW1") (pin "3") (pinfunction "3_3") (pintype "input"))
      (node (ref "SW1") (pin "4") (pinfunction "4_4") (pintype "input"))
      (node (ref "SW2") (pin "1") (pinfunction "1_1") (pintype "input"))
      (node (ref "SW2") (pin "3") (pinfunction "3_3") (pintype "input"))
      (node (ref "SW2") (pin "4") (pinfunction "4_4") (pintype "input"))
      (node (ref "SW4") (pin "2") (pinfunction "2_2") (pintype "input"))
      (node (ref "SW4") (pin "3") (pinfunction "3_3") (pintype "input"))
      (node (ref "SW4") (pin "4") (pinfunction "4_4") (pintype "input"))
      (node (ref "U1") (pin "49") (pinfunction "GND_49") (pintype "unspecified"))
      (node (ref "U2") (pin "2") (pinfunction "GND_2") (pintype "input"))
      (node (ref "U3") (pin "1") (pinfunction "A1_1") (pintype "unspecified"))
      (node (ref "U3") (pin "2") (pinfunction "A0_2") (pintype "unspecified"))
      (node (ref "U3") (pin "7") (pinfunction "GND_7") (pintype "unspecified"))
      (node (ref "U4") (pin "B3") (pinfunction "A0_B3") (pintype "input"))
      (node (ref "U4") (pin "C1") (pinfunction "GND_C1") (pintype "input"))
      (node (ref "U4") (pin "C3") (pinfunction "A1_C3") (pintype "input"))
      (node (ref "U5") (pin "15") (pinfunction "EP_15") (pintype "input"))
      (node (ref "U5") (pin "8") (pinfunction "GND_8") (pintype "input"))
      (node (ref "U5") (pin "9") (pinfunction "GND_9") (pintype "input"))
      (node (ref "USB1") (pin "1") (pinfunction "EH_1") (pintype "unspecified"))
      (node (ref "USB1") (pin "2") (pinfunction "EH_2") (pintype "unspecified"))
      (node (ref "USB1") (pin "A1") (pinfunction "GND_A1") (pintype "unspecified"))
      (node (ref "USB1") (pin "A12") (pinfunction "GND_A12") (pintype "unspecified"))
      (node (ref "USB1") (pin "B1") (pinfunction "GND_B1") (pintype "unspecified"))
      (node (ref "USB1") (pin "B12") (pinfunction "GND_B12") (pintype "unspecified"))
      (node (ref "USB3") (pin "25") (pinfunction "SHELL_25") (pintype "unspecified"))
      (node (ref "USB3") (pin "26") (pinfunction "SHELL_26") (pintype "unspecified"))
      (node (ref "USB3") (pin "A1") (pinfunction "GND_A1") (pintype "unspecified"))
      (node (ref "USB3") (pin "A12") (pinfunction "GND_A12") (pintype "unspecified"))
      (node (ref "USB3") (pin "B1") (pinfunction "GND_B1") (pintype "unspecified"))
      (node (ref "USB3") (pin "B12") (pinfunction "GND_B12") (pintype "unspecified"))
      (node (ref "USB4") (pin "25") (pinfunction "SHELL_25") (pintype "unspecified"))
      (node (ref "USB4") (pin "26") (pinfunction "SHELL_26") (pintype "unspecified"))
      (node (ref "USB4") (pin "A1") (pinfunction "GND_A1") (pintype "unspecified"))
      (node (ref "USB4") (pin "A12") (pinfunction "GND_A12") (pintype "unspecified"))
      (node (ref "USB4") (pin "B1") (pinfunction "GND_B1") (pintype "unspecified"))
      (node (ref "USB4") (pin "B12") (pinfunction "GND_B12") (pintype "unspecified"))
    )
    (net (code "38") (name "unconnected-(L2-Pad2)") (class "Default")
      (node (ref "L2") (pin "2") (pinfunction "2_2") (pintype "input"))
    )
    (net (code "39") (name "unconnected-(LCD1-NC-Pad9)") (class "Default")
      (node (ref "LCD1") (pin "9") (pinfunction "NC_9") (pintype "input+no_connect"))
    )
    (net (code "40") (name "unconnected-(LCD1-TP0-Pad1)") (class "Default")
      (node (ref "LCD1") (pin "1") (pinfunction "TP0_1") (pintype "input+no_connect"))
    )
    (net (code "41") (name "unconnected-(LCD1-TP1-Pad2)") (class "Default")
      (node (ref "LCD1") (pin "2") (pinfunction "TP1_2") (pintype "input+no_connect"))
    )
    (net (code "42") (name "unconnected-(LDO1-NC-Pad4)") (class "Default")
      (node (ref "LDO1") (pin "4") (pinfunction "NC_4") (pintype "input+no_connect"))
    )
    (net (code "43") (name "unconnected-(U1-CAP1_NC-Pad48)") (class "Default")
      (node (ref "U1") (pin "48") (pinfunction "CAP1_NC_48") (pintype "unspecified+no_connect"))
    )
    (net (code "44") (name "unconnected-(U1-CAP2_NC-Pad47)") (class "Default")
      (node (ref "U1") (pin "47") (pinfunction "CAP2_NC_47") (pintype "unspecified+no_connect"))
    )
    (net (code "45") (name "unconnected-(U1-CLK-Pad31)") (class "Default")
      (node (ref "U1") (pin "31") (pinfunction "CLK_31") (pintype "unspecified+no_connect"))
    )
    (net (code "46") (name "unconnected-(U1-CMD-Pad30)") (class "Default")
      (node (ref "U1") (pin "30") (pinfunction "CMD_30") (pintype "unspecified+no_connect"))
    )
    (net (code "47") (name "unconnected-(U1-IO16-Pad25)") (class "Default")
      (node (ref "U1") (pin "25") (pinfunction "IO16_25") (pintype "unspecified+no_connect"))
    )
    (net (code "48") (name "unconnected-(U1-IO17-Pad27)") (class "Default")
      (node (ref "U1") (pin "27") (pinfunction "IO17_27") (pintype "unspecified+no_connect"))
    )
    (net (code "49") (name "unconnected-(U1-IO18-Pad35)") (class "Default")
      (node (ref "U1") (pin "35") (pinfunction "IO18_35") (pintype "unspecified"))
    )
    (net (code "50") (name "unconnected-(U1-IO32-Pad12)") (class "Default")
      (node (ref "U1") (pin "12") (pinfunction "IO32_12") (pintype "unspecified+no_connect"))
    )
    (net (code "51") (name "unconnected-(U1-IO34-Pad10)") (class "Default")
      (node (ref "U1") (pin "10") (pinfunction "IO34_10") (pintype "unspecified+no_connect"))
    )
    (net (code "52") (name "unconnected-(U1-SD0-Pad32)") (class "Default")
      (node (ref "U1") (pin "32") (pinfunction "SD0_32") (pintype "unspecified+no_connect"))
    )
    (net (code "53") (name "unconnected-(U1-SD1-Pad33)") (class "Default")
      (node (ref "U1") (pin "33") (pinfunction "SD1_33") (pintype "unspecified+no_connect"))
    )
    (net (code "54") (name "unconnected-(U1-SD2-Pad28)") (class "Default")
      (node (ref "U1") (pin "28") (pinfunction "SD2_28") (pintype "unspecified+no_connect"))
    )
    (net (code "55") (name "unconnected-(U1-SD3-Pad29)") (class "Default")
      (node (ref "U1") (pin "29") (pinfunction "SD3_29") (pintype "unspecified+no_connect"))
    )
    (net (code "56") (name "unconnected-(U1-SENSOR_CAPN-Pad7)") (class "Default")
      (node (ref "U1") (pin "7") (pinfunction "SENSOR_CAPN_7") (pintype "unspecified+no_connect"))
    )
    (net (code "57") (name "unconnected-(U1-SENSOR_CAPP-Pad6)") (class "Default")
      (node (ref "U1") (pin "6") (pinfunction "SENSOR_CAPP_6") (pintype "unspecified+no_connect"))
    )
    (net (code "58") (name "unconnected-(U1-SENSOR_VN-Pad8)") (class "Default")
      (node (ref "U1") (pin "8") (pinfunction "SENSOR_VN_8") (pintype "unspecified+no_connect"))
    )
    (net (code "59") (name "unconnected-(U1-VDD_SDIO-Pad26)") (class "Default")
      (node (ref "U1") (pin "26") (pinfunction "VDD_SDIO_26") (pintype "unspecified+no_connect"))
    )
    (net (code "60") (name "unconnected-(U1-XTAL_N_NC-Pad44)") (class "Default")
      (node (ref "U1") (pin "44") (pinfunction "XTAL_N_NC_44") (pintype "unspecified+no_connect"))
    )
    (net (code "61") (name "unconnected-(U1-XTAL_P_NC-Pad45)") (class "Default")
      (node (ref "U1") (pin "45") (pinfunction "XTAL_P_NC_45") (pintype "unspecified+no_connect"))
    )
    (net (code "62") (name "unconnected-(U3-Alert-Pad3)") (class "Default")
      (node (ref "U3") (pin "3") (pinfunction "Alert_3") (pintype "unspecified+no_connect"))
    )
    (net (code "63") (name "unconnected-(U4-ALERT-PadA3)") (class "Default")
      (node (ref "U4") (pin "A3") (pinfunction "ALERT_A3") (pintype "input+no_connect"))
    )
    (net (code "64") (name "unconnected-(U4-NC-PadB2)") (class "Default")
      (node (ref "U4") (pin "B2") (pinfunction "NC_B2") (pintype "input+no_connect"))
    )
    (net (code "65") (name "unconnected-(U4-NC-PadC2)") (class "Default")
      (node (ref "U4") (pin "C2") (pinfunction "NC_C2") (pintype "input"))
    )
    (net (code "66") (name "unconnected-(U5-VBUS-Pad2)") (class "Default")
      (node (ref "U5") (pin "2") (pinfunction "VBUS_2") (pintype "input+no_connect"))
    )
    (net (code "67") (name "unconnected-(USB1-D+-PadA6)") (class "Default")
      (node (ref "USB1") (pin "A6") (pinfunction "D+_A6") (pintype "unspecified+no_connect"))
    )
    (net (code "68") (name "unconnected-(USB1-D--PadA7)") (class "Default")
      (node (ref "USB1") (pin "A7") (pinfunction "D-_A7") (pintype "unspecified+no_connect"))
    )
    (net (code "69") (name "unconnected-(USB1-RX1+-PadB11)") (class "Default")
      (node (ref "USB1") (pin "B11") (pinfunction "RX1+_B11") (pintype "unspecified+no_connect"))
    )
    (net (code "70") (name "unconnected-(USB1-RX1--PadB10)") (class "Default")
      (node (ref "USB1") (pin "B10") (pinfunction "RX1-_B10") (pintype "unspecified+no_connect"))
    )
    (net (code "71") (name "unconnected-(USB1-RX2+-PadA11)") (class "Default")
      (node (ref "USB1") (pin "A11") (pinfunction "RX2+_A11") (pintype "unspecified+no_connect"))
    )
    (net (code "72") (name "unconnected-(USB1-RX2--PadA10)") (class "Default")
      (node (ref "USB1") (pin "A10") (pinfunction "RX2-_A10") (pintype "unspecified+no_connect"))
    )
    (net (code "73") (name "unconnected-(USB1-TX1+-PadA2)") (class "Default")
      (node (ref "USB1") (pin "A2") (pinfunction "TX1+_A2") (pintype "unspecified+no_connect"))
    )
    (net (code "74") (name "unconnected-(USB1-TX1--PadA3)") (class "Default")
      (node (ref "USB1") (pin "A3") (pinfunction "TX1-_A3") (pintype "unspecified+no_connect"))
    )
    (net (code "75") (name "unconnected-(USB1-TX2+-PadB2)") (class "Default")
      (node (ref "USB1") (pin "B2") (pinfunction "TX2+_B2") (pintype "unspecified+no_connect"))
    )
    (net (code "76") (name "unconnected-(USB1-TX2--PadB3)") (class "Default")
      (node (ref "USB1") (pin "B3") (pinfunction "TX2-_B3") (pintype "unspecified+no_connect"))
    )
    (net (code "77") (name "unconnected-(USB3-SSRXN1-PadB10)") (class "Default")
      (node (ref "USB3") (pin "B10") (pinfunction "SSRXN1_B10") (pintype "unspecified+no_connect"))
    )
    (net (code "78") (name "unconnected-(USB3-SSRXN2-PadA10)") (class "Default")
      (node (ref "USB3") (pin "A10") (pinfunction "SSRXN2_A10") (pintype "unspecified+no_connect"))
    )
    (net (code "79") (name "unconnected-(USB3-SSRXP1-PadB11)") (class "Default")
      (node (ref "USB3") (pin "B11") (pinfunction "SSRXP1_B11") (pintype "unspecified+no_connect"))
    )
    (net (code "80") (name "unconnected-(USB3-SSRXP2-PadA11)") (class "Default")
      (node (ref "USB3") (pin "A11") (pinfunction "SSRXP2_A11") (pintype "unspecified+no_connect"))
    )
    (net (code "81") (name "unconnected-(USB3-SSTXN1-PadA3)") (class "Default")
      (node (ref "USB3") (pin "A3") (pinfunction "SSTXN1_A3") (pintype "unspecified+no_connect"))
    )
    (net (code "82") (name "unconnected-(USB3-SSTXN2-PadB3)") (class "Default")
      (node (ref "USB3") (pin "B3") (pinfunction "SSTXN2_B3") (pintype "unspecified+no_connect"))
    )
    (net (code "83") (name "unconnected-(USB3-SSTXP1-PadA2)") (class "Default")
      (node (ref "USB3") (pin "A2") (pinfunction "SSTXP1_A2") (pintype "unspecified+no_connect"))
    )
    (net (code "84") (name "unconnected-(USB3-SSTXP2-PadB2)") (class "Default")
      (node (ref "USB3") (pin "B2") (pinfunction "SSTXP2_B2") (pintype "unspecified+no_connect"))
    )
    (net (code "85") (name "unconnected-(USB4-SSRXN1-PadB10)") (class "Default")
      (node (ref "USB4") (pin "B10") (pinfunction "SSRXN1_B10") (pintype "unspecified+no_connect"))
    )
    (net (code "86") (name "unconnected-(USB4-SSRXN2-PadA10)") (class "Default")
      (node (ref "USB4") (pin "A10") (pinfunction "SSRXN2_A10") (pintype "unspecified+no_connect"))
    )
    (net (code "87") (name "unconnected-(USB4-SSRXP1-PadB11)") (class "Default")
      (node (ref "USB4") (pin "B11") (pinfunction "SSRXP1_B11") (pintype "unspecified+no_connect"))
    )
    (net (code "88") (name "unconnected-(USB4-SSRXP2-PadA11)") (class "Default")
      (node (ref "USB4") (pin "A11") (pinfunction "SSRXP2_A11") (pintype "unspecified+no_connect"))
    )
    (net (code "89") (name "unconnected-(USB4-SSTXN1-PadA3)") (class "Default")
      (node (ref "USB4") (pin "A3") (pinfunction "SSTXN1_A3") (pintype "unspecified+no_connect"))
    )
    (net (code "90") (name "unconnected-(USB4-SSTXN2-PadB3)") (class "Default")
      (node (ref "USB4") (pin "B3") (pinfunction "SSTXN2_B3") (pintype "unspecified+no_connect"))
    )
    (net (code "91") (name "unconnected-(USB4-SSTXP1-PadA2)") (class "Default")
      (node (ref "USB4") (pin "A2") (pinfunction "SSTXP1_A2") (pintype "unspecified+no_connect"))
    )
    (net (code "92") (name "unconnected-(USB4-SSTXP2-PadB2)") (class "Default")
      (node (ref "USB4") (pin "B2") (pinfunction "SSTXP2_B2") (pintype "unspecified+no_connect"))
    )
  )
)
